# maxwell_dev_board.net
KiCad netlist of a schematic drawn in Altium Designer
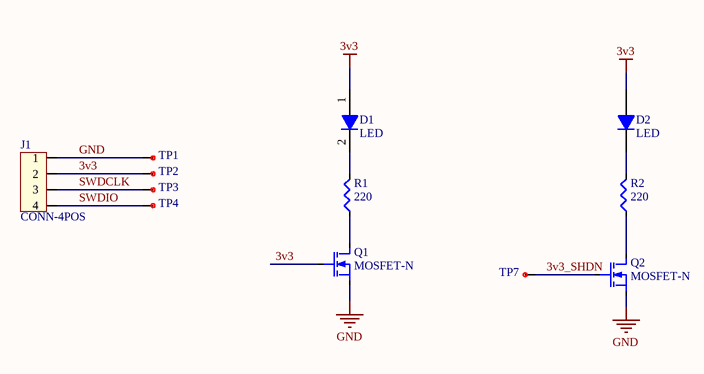
[diagram p0: maxwell_dev_board.SchDoc]

(export (version "E")
  (design (tool "Eeschema 10.0.6"))
  (components
    (comp (ref "D1")
      (value "LED")
      (footprint "LED_0603")
      (description "Default Diode")
      (fields
        (field (name "PARTNUMBER") "3372-0603GBD0790S01TR-ND")
        (field (name "PUBLISHER") "Altium Limited")
      )
      (libsource (lib "ha_lib") (part "LED"))
    )
    (comp (ref "D2")
      (value "LED")
      (footprint "LED_0603")
      (description "Default Diode")
      (fields (field (name "PUBLISHER") "Altium Limited"))
      (libsource (lib "") (part "LED_1"))
    )
    (comp (ref "J1")
      (value "CONN-4POS")
      (footprint "4_PIN_HEADER")
      (libsource (lib "maxwell_dev_board") (part "CONN-4POS"))
    )
    (comp (ref "Q1")
      (value "MOSFET-N")
      (footprint "SOT-23")
      (description "N-Channel MOSFET")
      (fields (field (name "PUBLISHER") "Altium Limited"))
      (libsource (lib "ha_lib") (part "MOSFET-N"))
    )
    (comp (ref "Q2")
      (value "MOSFET-N")
      (footprint "SOT-23")
      (description "N-Channel MOSFET")
      (fields (field (name "PUBLISHER") "Altium Limited"))
      (libsource (lib "ha_lib") (part "MOSFET-N"))
    )
    (comp (ref "R1")
      (value "220")
      (footprint "RES0603")
      (description "Chip Resistor")
      (fields (field (name "PUBLISHER") "HabitAware"))
      (libsource (lib "maxwell_dev_board") (part "RES"))
    )
    (comp (ref "R2")
      (value "220")
      (footprint "RES0603")
      (description "Chip Resistor")
      (fields (field (name "PUBLISHER") "HabitAware"))
      (libsource (lib "maxwell_dev_board") (part "RES"))
    )
    (comp (ref "TP1")
      (value "TEST_PIN")
      (footprint "TEST_PIN")
      (libsource (lib "maxwell_dev_board") (part "TEST_PIN"))
    )
    (comp (ref "TP2")
      (value "TEST_PIN")
      (footprint "TEST_PIN")
      (libsource (lib "maxwell_dev_board") (part "TEST_PIN"))
    )
    (comp (ref "TP3")
      (value "TEST_PIN")
      (footprint "TEST_PIN")
      (libsource (lib "maxwell_dev_board") (part "TEST_PIN"))
    )
    (comp (ref "TP4")
      (value "TEST_PIN")
      (footprint "TEST_PIN")
      (libsource (lib "maxwell_dev_board") (part "TEST_PIN"))
    )
    (comp (ref "TP7")
      (value "TEST_PIN")
      (footprint "TEST_PIN")
      (libsource (lib "maxwell_dev_board") (part "TEST_PIN"))
    )
  )
  (nets
    (net (code "1") (name "/3v3_SHDN") (class "Default")
      (node (ref "Q2") (pin "1") (pinfunction "G_1") (pintype "passive"))
      (node (ref "TP7") (pin "1") (pinfunction "1_1") (pintype "passive"))
    )
    (net (code "2") (name "/SWDCLK") (class "Default")
      (node (ref "J1") (pin "3") (pinfunction "3_3") (pintype "passive"))
      (node (ref "TP3") (pin "1") (pinfunction "1_1") (pintype "passive"))
    )
    (net (code "3") (name "/SWDIO") (class "Default")
      (node (ref "J1") (pin "4") (pinfunction "4_4") (pintype "passive"))
      (node (ref "TP4") (pin "1") (pinfunction "1_1") (pintype "passive"))
    )
    (net (code "4") (name "3v3") (class "Default")
      (node (ref "D1") (pin "1") (pinfunction "A_1") (pintype "passive"))
      (node (ref "D2") (pin "1") (pinfunction "A_1") (pintype "passive"))
      (node (ref "J1") (pin "2") (pinfunction "2_2") (pintype "passive"))
      (node (ref "Q1") (pin "1") (pinfunction "G_1") (pintype "passive"))
      (node (ref "TP2") (pin "1") (pinfunction "1_1") (pintype "passive"))
    )
    (net (code "5") (name "GND") (class "Default")
      (node (ref "J1") (pin "1") (pinfunction "1_1") (pintype "passive"))
      (node (ref "Q1") (pin "2") (pinfunction "S_2") (pintype "passive"))
      (node (ref "Q2") (pin "2") (pinfunction "S_2") (pintype "passive"))
      (node (ref "TP1") (pin "1") (pinfunction "1_1") (pintype "passive"))
    )
    (net (code "6") (name "Net-(D1-K)") (class "Default")
      (node (ref "D1") (pin "2") (pinfunction "K_2") (pintype "passive"))
      (node (ref "R1") (pin "2") (pinfunction "2_2") (pintype "passive"))
    )
    (net (code "7") (name "Net-(D2-K)") (class "Default")
      (node (ref "D2") (pin "2") (pinfunction "K_2") (pintype "passive"))
      (node (ref "R2") (pin "2") (pinfunction "2_2") (pintype "passive"))
    )
    (net (code "8") (name "Net-(Q1-D)") (class "Default")
      (node (ref "Q1") (pin "3") (pinfunction "D_3") (pintype "passive"))
      (node (ref "R1") (pin "1") (pinfunction "1_1") (pintype "passive"))
    )
    (net (code "9") (name "Net-(Q2-D)") (class "Default")
      (node (ref "Q2") (pin "3") (pinfunction "D_3") (pintype "passive"))
      (node (ref "R2") (pin "1") (pinfunction "1_1") (pintype "passive"))
    )
  )
)
